# 12V_FROM_BATTERY.net
KiCad netlist of a schematic drawn in Altium Designer
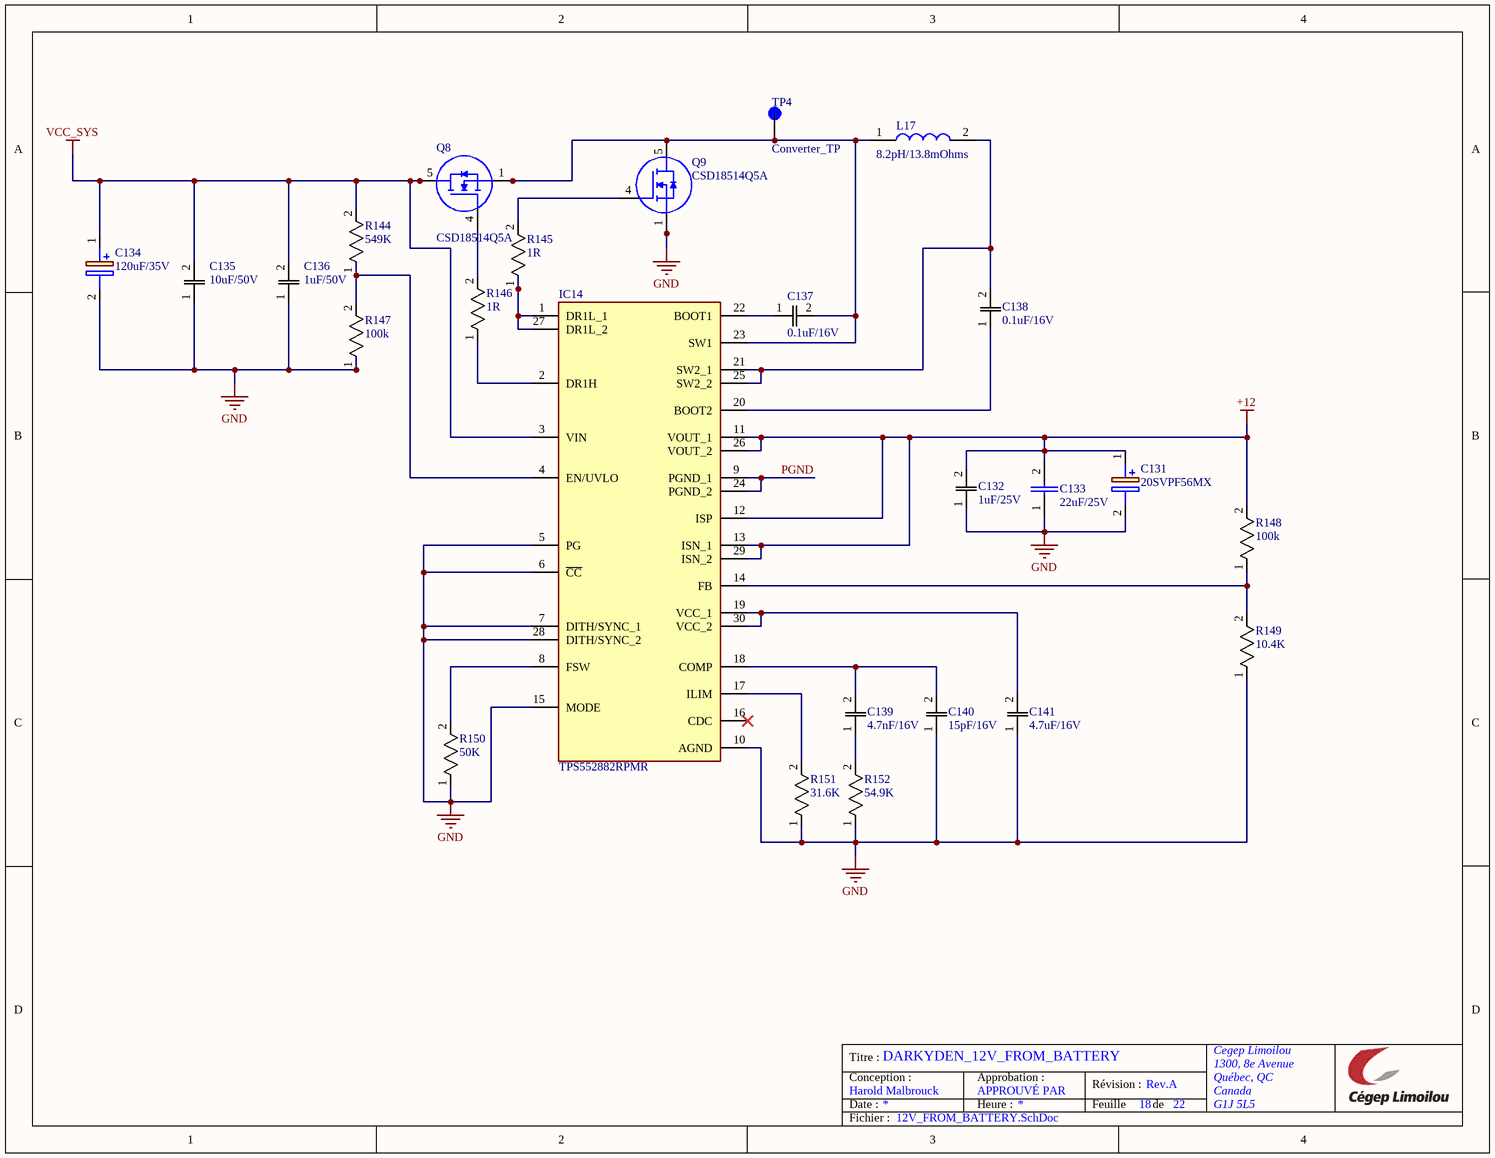
[diagram p0: 12V_FROM_BATTERY.SchDoc]

(export (version "E")
  (design (tool "Eeschema 10.0.6"))
  (components
    (comp (ref "C131")
      (value "20SVPF56MX")
      (footprint "SamacSys:16SVF82M")
      (description "56uF 20VDC 20%( Cap Aluminum Polymer SMD 0.03 Ohm 2800mA 5000h 105C T/R")
      (fields (field (name "MOUSER PART NUMBER") "667-20SVPF56MX") (field (name "MANUFACTURER") "Panasonic"))
      (libsource (lib "SamacSys") (part "20SVPF56MX"))
    )
    (comp (ref "C132")
      (value "1uF/25V")
      (footprint "C0805")
      (description "1 µF, 25 V (DC), ±10 %, SMD 0805, X7R, C0805C105K3RAC7800")
      (fields
        (field (name "MANUFACTURER_PART_NUMBER") "C0805C105K3RACTU")
        (field (name "MOUSER PART NUMBER") "80-C0805C105K3R")
      )
      (libsource (lib "DARKYDEN") (part "C0805C105K3RACTU"))
    )
    (comp (ref "C133")
      (value "22uF/25V")
      (footprint "SamacSys:CAPC3225X270N")
      (description "1210 22 uF 25 V ±10% Tolerance X5R SMT Multilayer Ceramic Capacitor")
      (fields
        (field (name "MANUFACTURER_PART_NUMBER") "GRM32ER61E226KE15L")
        (field (name "MOUSER PART NUMBER") "81-GRM32ER61E226KE15")
      )
      (libsource (lib "SamacSys") (part "GRM32ER61E226KE15L"))
    )
    (comp (ref "C134")
      (value "120uF/35V")
      (footprint "SamacSys:16SVF1000M")
      (description "120uF 35VDC 20% Cap Aluminum Polymer   SMD 0.018 Ohm 4400mA 5000h 105C T/R")
      (fields
        (field (name "MANUFACTURER_PART_NUMBER") "35SVPF120M")
        (field (name "MOUSER PART NUMBER") "667-35SVPF120M")
      )
      (libsource (lib "SamacSys") (part "35SVPF120M"))
    )
    (comp (ref "C135")
      (value "10uF/50V")
      (footprint "SamacSys:CAPC3225X230N")
      (description "10 uF 50 V 1210 ±20 % Tolerance X7R SMT Multilayer Ceramic Capacitor")
      (fields
        (field (name "MANUFACTURER_PART_NUMBER") "C3225X7R1H106M250AC")
        (field (name "MOUSER PART NUMBER") "810-C3225X7R1H106MAC")
      )
      (libsource (lib "SamacSys") (part "C3225X7R1H106M250AC"))
    )
    (comp (ref "C136")
      (value "1uF/50V")
      (footprint "SamacSys:CAPC1608X80N")
      (description "1uF / 50 V, X5R,  Surface Mount, 0603")
      (fields
        (field (name "MANUFACTURER_PART_NUMBER") "C1608X5R1H105K080AB")
        (field (name "MOUSER PART NUMBER") "810-C1608X5R1H105K")
      )
      (libsource (lib "SamacSys") (part "C1608X5R1H105K080AB"))
    )
    (comp (ref "C137")
      (value "0.1uF/16V")
      (footprint "C0805")
      (description "0.1uF/16V ±10% X7R 0805 (2012METRIC) Ceramic Capacitor SMD Auto X7R")
      (fields
        (field (name "MANUFACTURER") "KEMET")
        (field (name "MANUFACTURER PART NUMBER") "C0805C104K4RACAUTO")
      )
      (libsource (lib "DARKYDEN") (part "C0805C104K4RACAUTO"))
    )
    (comp (ref "C138")
      (value "0.1uF/16V")
      (footprint "C0805")
      (description "0.1uF/16V ±10% X7R 0805 (2012METRIC) Ceramic Capacitor SMD Auto X7R")
      (fields
        (field (name "MANUFACTURER") "KEMET")
        (field (name "MANUFACTURER PART NUMBER") "C0805C104K4RACAUTO")
      )
      (libsource (lib "DARKYDEN") (part "C0805C104K4RACAUTO"))
    )
    (comp (ref "C139")
      (value "4.7nF/16V")
      (footprint "c0805")
      (description "4.7nF, 16VDC, 10-% Tol, 10+% Tol, X7R-TC Code, -15, 15%-TC RoHS Compliant: Yes")
      (fields
        (field (name "MANUFACTURER") "KEMET")
        (field (name "MANUFACTURER PART NUMBER") "C0805C472K4RACTU")
      )
      (libsource (lib "DARKYDEN") (part "C0805C472K4RACTU"))
    )
    (comp (ref "C140")
      (value "15pF/16V")
      (footprint "C0805")
      (description "15 pF, 16 V, ± 10%, C0G (NP0), 0805 [2012 Metric]")
      (fields
        (field (name "MANUFACTURER") "KEMET")
        (field (name "MANUFACTURER PART NUMBER") "C0805C150K4GACTU")
      )
      (libsource (lib "DARKYDEN") (part "C0805C150K4GACTU"))
    )
    (comp (ref "C141")
      (value "4.7uF/16V")
      (footprint "C0805")
      (description "4.7 uF, 16 V, ± 10%, X7R, 0805 [2012 Metric]")
      (fields
        (field (name "MANUFACTURER_PART_NUMBER") "C0805C475K4RACTU")
        (field (name "MOUSER PART NUMBER") "80-C0805C475K4R")
      )
      (libsource (lib "DARKYDEN") (part "C0805C475K4RACTU"))
    )
    (comp (ref "IC14")
      (value "TPS552882RPMR")
      (footprint "SamacSys:TPS552882RPMR")
      (description "36-V, 16-A buck-boost converter 26-VQFN-HR -40 to 125")
      (fields
        (field (name "MOUSER PART NUMBER") "595-TPS552882RPMR")
        (field (name "MANUFACTURER") "Texas Instruments")
      )
      (libsource (lib "SamacSys") (part "TPS552882RPMR"))
    )
    (comp (ref "L17")
      (value "8.2pH/13.8mOhms")
      (footprint "SamacSys:INDPM135126X650N")
      (description "Inductor Power Shielded/Molded Wirewound 8.2uH 20% 100KHz 15A 0.0138Ohm DCR Automotive T/R")
      (fields
        (field (name "MANUFACTURER_PART_NUMBER") "PA4343.822ANLT")
        (field (name "MOUSER PART NUMBER") "673-PA4343.822ANLT")
      )
      (libsource (lib "SamacSys") (part "PA4343.822ANLT"))
    )
    (comp (ref "Q8")
      (value "CSD18514Q5A")
      (footprint "SamacSys:CSD18514Q5A")
      (description "MOSFET N-Channel 40 V 89A (Tc) 74W (Tc) Surface Mount 8-VSONP (5x6)")
      (fields (field (name "MOUSER PART NUMBER") "595-CSD18514Q5A"))
      (libsource (lib "SamacSys") (part "CSD18514Q5A"))
    )
    (comp (ref "Q9")
      (value "CSD18514Q5A")
      (footprint "SamacSys:CSD18514Q5A")
      (description "MOSFET N-Channel 40 V 89A (Tc) 74W (Tc) Surface Mount 8-VSONP (5x6)")
      (fields (field (name "MOUSER PART NUMBER") "595-CSD18514Q5A"))
      (libsource (lib "SamacSys") (part "CSD18514Q5A"))
    )
    (comp (ref "R144")
      (value "549K")
      (footprint "RESC1608X55N")
      (description "549 kOhm, ± 1%, 100 mW, 0603 [1608 Metric], Thick Film, Precision")
      (fields
        (field (name "MANUFACTURER") "Panasonic")
        (field (name "MANUFACTURER PART NUMBER") "ERJ-3EKF5493V")
      )
      (libsource (lib "DARKYDEN") (part "ERJ-3EKF5493V"))
    )
    (comp (ref "R145")
      (value "1R")
      (footprint "SamacSys:RESC1608X55N")
      (description "1 Ohm 5% 1/10W  Res Thick Film 0603 -100ppm/ t¦")
      (fields
        (field (name "MANUFACTURER_PART_NUMBER") "ERJ-3GEYJ1R0V")
        (field (name "MOUSER PART NUMBER") "667-ERJ-3GEYJ1R0V")
      )
      (libsource (lib "DARKYDEN") (part "ERJ-3GEYJ1R0V"))
    )
    (comp (ref "R146")
      (value "1R")
      (footprint "SamacSys:RESC1608X55N")
      (description "1 Ohm 5% 1/10W  Res Thick Film 0603 -100ppm/ t¦")
      (fields
        (field (name "MANUFACTURER_PART_NUMBER") "ERJ-3GEYJ1R0V")
        (field (name "MOUSER PART NUMBER") "667-ERJ-3GEYJ1R0V")
      )
      (libsource (lib "DARKYDEN") (part "ERJ-3GEYJ1R0V"))
    )
    (comp (ref "R147")
      (value "100k")
      (footprint "SamacSys:RESC1608X55N")
      (description "100K Ohm 5%  Res Thick Film 0603 1/10W +/-200ppm/ßC Molded SMD Punched Carrier T/R")
      (fields
        (field (name "MANUFACTURER_PART_NUMBER") "ERJ-3GEYJ104V")
        (field (name "MOUSER PART NUMBER") "667-ERJ-3GEYJ104V")
      )
      (libsource (lib "DARKYDEN") (part "ERJ-3GEYJ104V"))
    )
    (comp (ref "R148")
      (value "100k")
      (footprint "SamacSys:RESC1608X55N")
      (description "100K Ohm 5%  Res Thick Film 0603 1/10W +/-200ppm/ßC Molded SMD Punched Carrier T/R")
      (fields
        (field (name "MANUFACTURER_PART_NUMBER") "ERJ-3GEYJ104V")
        (field (name "MOUSER PART NUMBER") "667-ERJ-3GEYJ104V")
      )
      (libsource (lib "DARKYDEN") (part "ERJ-3GEYJ104V"))
    )
    (comp (ref "R149")
      (value "10.4K")
      (footprint "RESC1608X55N")
      (description "10.4kOhm 0.1% High Precision-High Stability Chip Resistor Thin Film 0603  Paper T/R")
      (fields (field (name "MP") "RT0603BRD0710K4L") (field (name "MANUFACTURER") "Yageo"))
      (libsource (lib "DARKYDEN") (part "RT0603BRD0710K4L"))
    )
    (comp (ref "R150")
      (value "50K")
      (footprint "SamacSys:RESC1005X40N")
      (description "50 kΩ  Tolerance: 1.0%  Power: 63 mW  Package:0402")
      (fields
        (field (name "MANUFACTURER_PART_NUMBER") "CRCW040250K0FKED")
        (field (name "MOUSER PART NUMBER") "71-CRCW0402-50K-E3")
      )
      (libsource (lib "SamacSys") (part "CRCW040250K0FKED"))
    )
    (comp (ref "R151")
      (value "31.6K")
      (footprint "SamacSys:RESC1005X40N")
      (description "31.6 kΩ  Tolerance: 1.0%  Power: 63 mW")
      (fields
        (field (name "MANUFACTURER_PART_NUMBER") "CRCW040231K6FKED")
        (field (name "MOUSER PART NUMBER") "71-CRCW0402-31.6K-E3")
      )
      (libsource (lib "SamacSys") (part "CRCW040231K6FKED"))
    )
    (comp (ref "R152")
      (value "54.9K")
      (footprint "SamacSys:RESC1005X40N")
      (description "54.9 kΩ  Tolerance: 1.0%  Power: 63 mW  PAckage:0402")
      (fields
        (field (name "MANUFACTURER_PART_NUMBER") "CRCW040254K9FKED")
        (field (name "MOUSER PART NUMBER") "71-CRCW0402-54.9K-E3")
      )
      (libsource (lib "SamacSys") (part "CRCW040254K9FKED"))
    )
    (comp (ref "TP4")
      (value "Converter_TP")
      (footprint "KEYSTONE_5006")
      (description "Test Point Compact THM PC .350 L .125 OD Heat Resistant Nylon 46 Black ¦ Keystone Electronics 5006")
      (fields (field (name "MF") "Keystone Electronics Corp.") (field (name "MP") "5006"))
      (libsource (lib "test_point") (part "5006"))
    )
  )
  (nets
    (net (code "1") (name "+12") (class "Default")
      (node (ref "C131") (pin "1") (pinfunction "+_1") (pintype "passive"))
      (node (ref "C132") (pin "2") (pinfunction "2_2") (pintype "passive"))
      (node (ref "C133") (pin "2") (pinfunction "2_2") (pintype "passive"))
      (node (ref "IC14") (pin "11") (pinfunction "VOUT_1_11") (pintype "passive"))
      (node (ref "IC14") (pin "12") (pinfunction "ISP_12") (pintype "passive"))
      (node (ref "IC14") (pin "13") (pinfunction "ISN_1_13") (pintype "passive"))
      (node (ref "IC14") (pin "26") (pinfunction "VOUT_2_26") (pintype "passive"))
      (node (ref "IC14") (pin "29") (pinfunction "ISN_2_29") (pintype "passive"))
      (node (ref "R148") (pin "2") (pinfunction "2_2") (pintype "passive"))
    )
    (net (code "2") (name "/PGND") (class "Default")
      (node (ref "IC14") (pin "24") (pinfunction "PGND_2_24") (pintype "passive"))
      (node (ref "IC14") (pin "9") (pinfunction "PGND_1_9") (pintype "passive"))
    )
    (net (code "3") (name "GND") (class "Default")
      (node (ref "C131") (pin "2") (pinfunction "-_2") (pintype "passive"))
      (node (ref "C132") (pin "1") (pinfunction "1_1") (pintype "passive"))
      (node (ref "C133") (pin "1") (pinfunction "1_1") (pintype "passive"))
      (node (ref "C134") (pin "2") (pinfunction "-_2") (pintype "passive"))
      (node (ref "C135") (pin "1") (pinfunction "1_1") (pintype "passive"))
      (node (ref "C136") (pin "1") (pinfunction "1_1") (pintype "passive"))
      (node (ref "C140") (pin "1") (pinfunction "1_1") (pintype "passive"))
      (node (ref "C141") (pin "1") (pinfunction "1_1") (pintype "passive"))
      (node (ref "IC14") (pin "10") (pinfunction "AGND_10") (pintype "passive"))
      (node (ref "IC14") (pin "15") (pinfunction "MODE_15") (pintype "passive"))
      (node (ref "IC14") (pin "28") (pinfunction "DITH/SYNC_2_28") (pintype "passive"))
      (node (ref "IC14") (pin "5") (pinfunction "PG_5") (pintype "passive"))
      (node (ref "IC14") (pin "6") (pinfunction "~{CC}_6") (pintype "passive"))
      (node (ref "IC14") (pin "7") (pinfunction "DITH/SYNC_1_7") (pintype "passive"))
      (node (ref "Q9") (pin "1") (pinfunction "S_1") (pintype "passive"))
      (node (ref "Q9") (pin "2") (pinfunction "S_2_2") (pintype "passive"))
      (node (ref "Q9") (pin "3") (pinfunction "S_3_3") (pintype "passive"))
      (node (ref "R147") (pin "1") (pinfunction "1_1") (pintype "passive"))
      (node (ref "R149") (pin "1") (pinfunction "1_1") (pintype "passive"))
      (node (ref "R150") (pin "1") (pinfunction "1_1") (pintype "passive"))
      (node (ref "R151") (pin "1") (pinfunction "1_1") (pintype "passive"))
      (node (ref "R152") (pin "1") (pinfunction "1_1") (pintype "passive"))
    )
    (net (code "4") (name "Net-(C139-Pad1)") (class "Default")
      (node (ref "C139") (pin "1") (pinfunction "1_1") (pintype "passive"))
      (node (ref "R152") (pin "2") (pinfunction "2_2") (pintype "passive"))
    )
    (net (code "5") (name "Net-(IC14-BOOT1)") (class "Default")
      (node (ref "C137") (pin "1") (pinfunction "1_1") (pintype "passive"))
      (node (ref "IC14") (pin "22") (pinfunction "BOOT1_22") (pintype "passive"))
    )
    (net (code "6") (name "Net-(IC14-BOOT2)") (class "Default")
      (node (ref "C138") (pin "1") (pinfunction "1_1") (pintype "passive"))
      (node (ref "IC14") (pin "20") (pinfunction "BOOT2_20") (pintype "passive"))
    )
    (net (code "7") (name "Net-(IC14-COMP)") (class "Default")
      (node (ref "C139") (pin "2") (pinfunction "2_2") (pintype "passive"))
      (node (ref "C140") (pin "2") (pinfunction "2_2") (pintype "passive"))
      (node (ref "IC14") (pin "18") (pinfunction "COMP_18") (pintype "passive"))
    )
    (net (code "8") (name "Net-(IC14-DR1H)") (class "Default")
      (node (ref "IC14") (pin "2") (pinfunction "DR1H_2") (pintype "passive"))
      (node (ref "R146") (pin "1") (pinfunction "1_1") (pintype "passive"))
    )
    (net (code "9") (name "Net-(IC14-DR1L_1)") (class "Default")
      (node (ref "IC14") (pin "1") (pinfunction "DR1L_1_1") (pintype "passive"))
      (node (ref "IC14") (pin "27") (pinfunction "DR1L_2_27") (pintype "passive"))
      (node (ref "R145") (pin "1") (pinfunction "1_1") (pintype "passive"))
    )
    (net (code "10") (name "Net-(IC14-EN{slash}UVLO)") (class "Default")
      (node (ref "IC14") (pin "4") (pinfunction "EN/UVLO_4") (pintype "passive"))
      (node (ref "R144") (pin "1") (pinfunction "1_1") (pintype "passive"))
      (node (ref "R147") (pin "2") (pinfunction "2_2") (pintype "passive"))
    )
    (net (code "11") (name "Net-(IC14-FB)") (class "Default")
      (node (ref "IC14") (pin "14") (pinfunction "FB_14") (pintype "passive"))
      (node (ref "R148") (pin "1") (pinfunction "1_1") (pintype "passive"))
      (node (ref "R149") (pin "2") (pinfunction "2_2") (pintype "passive"))
    )
    (net (code "12") (name "Net-(IC14-FSW)") (class "Default")
      (node (ref "IC14") (pin "8") (pinfunction "FSW_8") (pintype "passive"))
      (node (ref "R150") (pin "2") (pinfunction "2_2") (pintype "passive"))
    )
    (net (code "13") (name "Net-(IC14-ILIM)") (class "Default")
      (node (ref "IC14") (pin "17") (pinfunction "ILIM_17") (pintype "passive"))
      (node (ref "R151") (pin "2") (pinfunction "2_2") (pintype "passive"))
    )
    (net (code "14") (name "Net-(IC14-SW1)") (class "Default")
      (node (ref "C137") (pin "2") (pinfunction "2_2") (pintype "passive"))
      (node (ref "IC14") (pin "23") (pinfunction "SW1_23") (pintype "passive"))
      (node (ref "L17") (pin "1") (pinfunction "1_1") (pintype "passive"))
      (node (ref "Q8") (pin "1") (pinfunction "S_1") (pintype "passive"))
      (node (ref "Q8") (pin "2") (pinfunction "S_2_2") (pintype "passive"))
      (node (ref "Q8") (pin "3") (pinfunction "S_3_3") (pintype "passive"))
      (node (ref "Q9") (pin "5") (pinfunction "D_5") (pintype "passive"))
      (node (ref "Q9") (pin "6") (pinfunction "D_2_6") (pintype "passive"))
      (node (ref "Q9") (pin "7") (pinfunction "D_3_7") (pintype "passive"))
      (node (ref "Q9") (pin "8") (pinfunction "D_4_8") (pintype "passive"))
      (node (ref "Q9") (pin "9") (pinfunction "D_5_9") (pintype "passive"))
      (node (ref "TP4") (pin "TP") (pinfunction "TP_TP") (pintype "passive"))
    )
    (net (code "15") (name "Net-(IC14-SW2_1)") (class "Default")
      (node (ref "C138") (pin "2") (pinfunction "2_2") (pintype "passive"))
      (node (ref "IC14") (pin "21") (pinfunction "SW2_1_21") (pintype "passive"))
      (node (ref "IC14") (pin "25") (pinfunction "SW2_2_25") (pintype "passive"))
      (node (ref "L17") (pin "2") (pinfunction "2_2") (pintype "passive"))
    )
    (net (code "16") (name "Net-(IC14-VCC_1)") (class "Default")
      (node (ref "C141") (pin "2") (pinfunction "2_2") (pintype "passive"))
      (node (ref "IC14") (pin "19") (pinfunction "VCC_1_19") (pintype "passive"))
      (node (ref "IC14") (pin "30") (pinfunction "VCC_2_30") (pintype "passive"))
    )
    (net (code "17") (name "Net-(Q8-G)") (class "Default")
      (node (ref "Q8") (pin "4") (pinfunction "G_4") (pintype "passive"))
      (node (ref "R146") (pin "2") (pinfunction "2_2") (pintype "passive"))
    )
    (net (code "18") (name "Net-(Q9-G)") (class "Default")
      (node (ref "Q9") (pin "4") (pinfunction "G_4") (pintype "passive"))
      (node (ref "R145") (pin "2") (pinfunction "2_2") (pintype "passive"))
    )
    (net (code "19") (name "VCC_SYS") (class "Default")
      (node (ref "C134") (pin "1") (pinfunction "+_1") (pintype "passive"))
      (node (ref "C135") (pin "2") (pinfunction "2_2") (pintype "passive"))
      (node (ref "C136") (pin "2") (pinfunction "2_2") (pintype "passive"))
      (node (ref "IC14") (pin "3") (pinfunction "VIN_3") (pintype "passive"))
      (node (ref "Q8") (pin "5") (pinfunction "D_5") (pintype "passive"))
      (node (ref "Q8") (pin "6") (pinfunction "D_2_6") (pintype "passive"))
      (node (ref "Q8") (pin "7") (pinfunction "D_3_7") (pintype "passive"))
      (node (ref "Q8") (pin "8") (pinfunction "D_4_8") (pintype "passive"))
      (node (ref "Q8") (pin "9") (pinfunction "D_5_9") (pintype "passive"))
      (node (ref "R144") (pin "2") (pinfunction "2_2") (pintype "passive"))
    )
    (net (code "20") (name "unconnected-(IC14-CDC-Pad16)") (class "Default")
      (node (ref "IC14") (pin "16") (pinfunction "CDC_16") (pintype "passive+no_connect"))
    )
  )
)
